# fnordlichtmini_v4.net
KiCad netlist of a schematic drawn in EAGLE
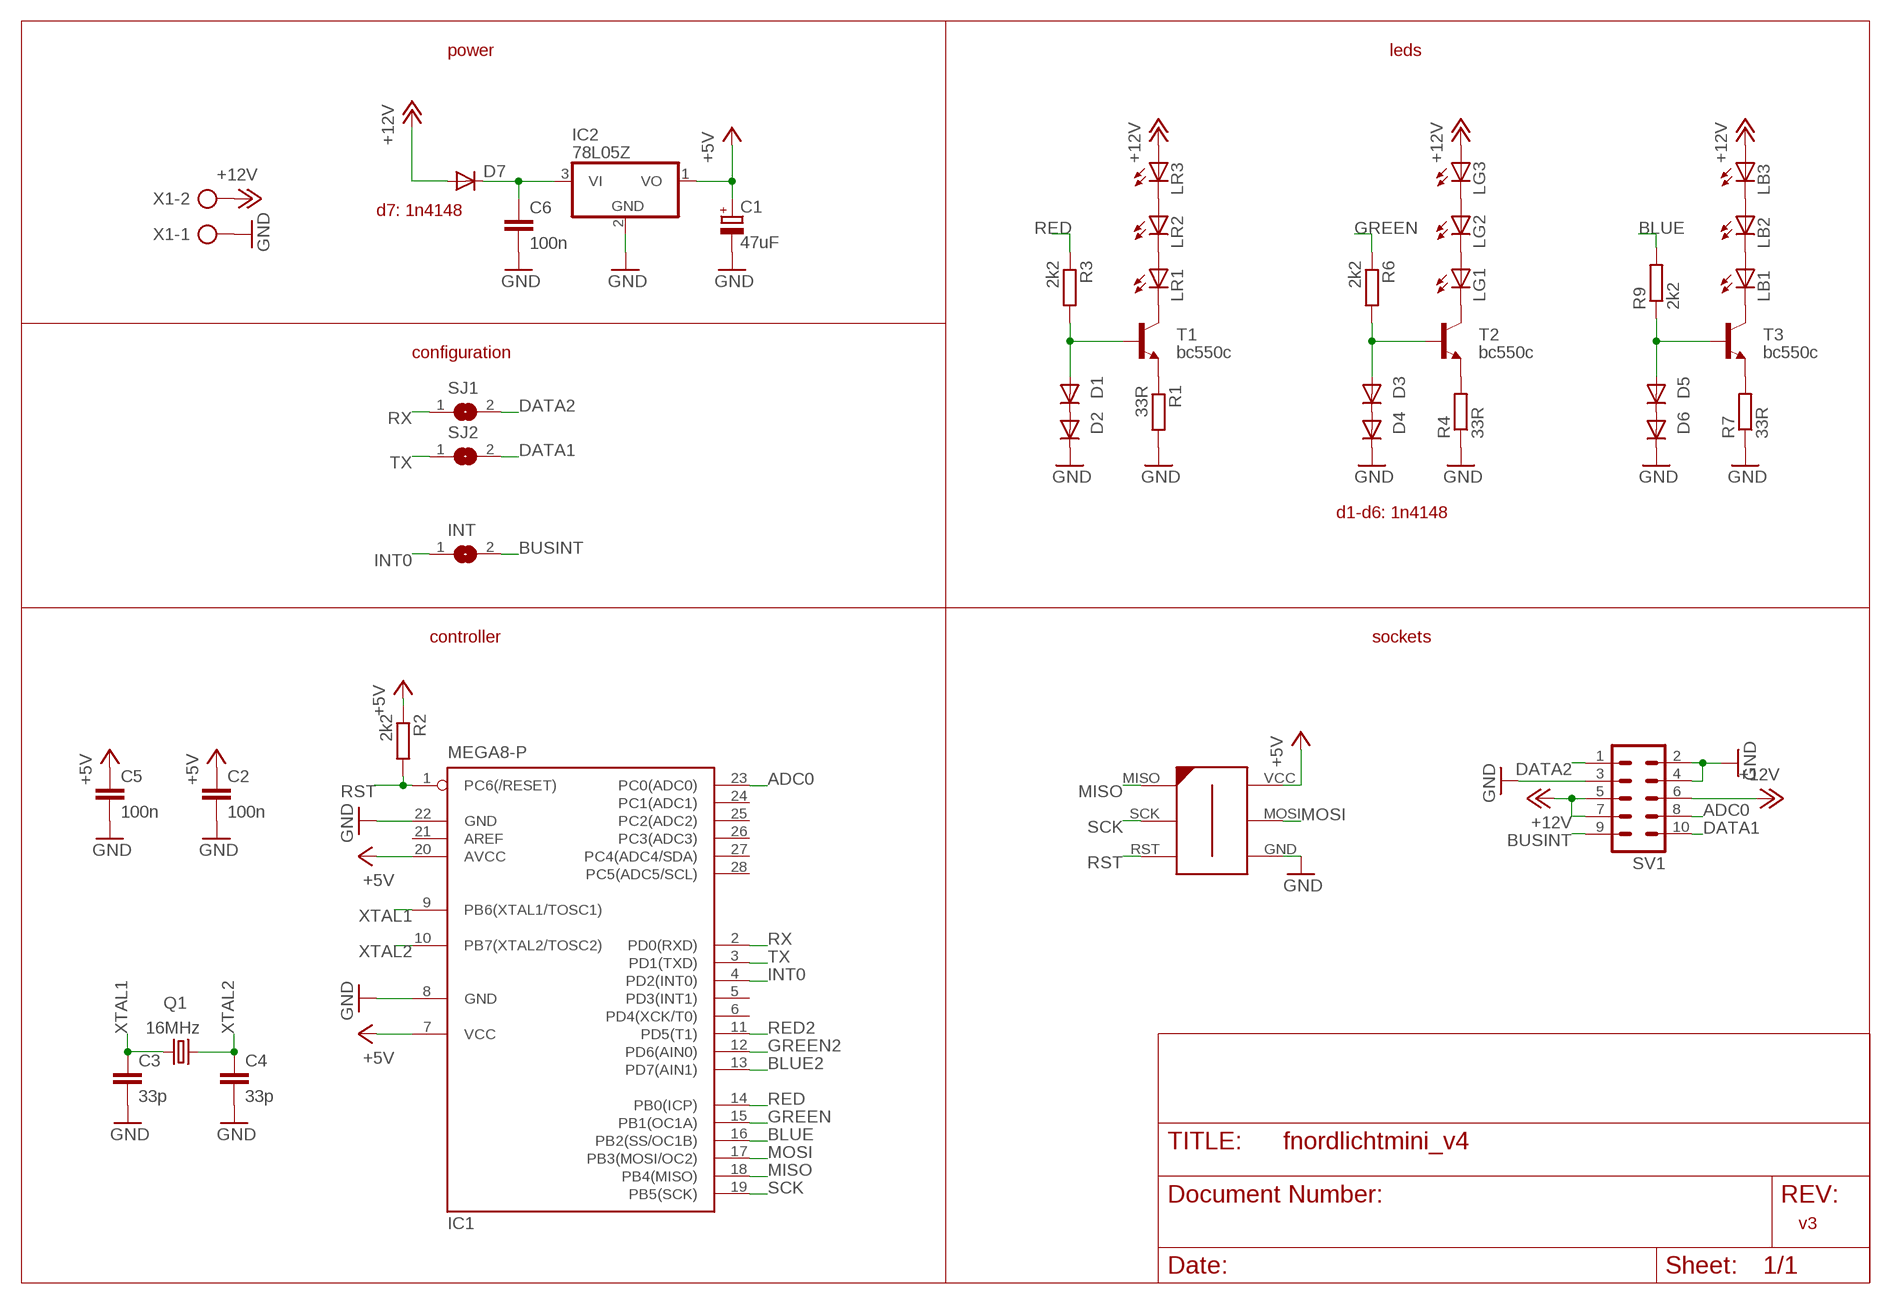
[diagram p0: schematic, sheet 1]

(export (version "E")
  (design (tool "Eeschema 10.0.6"))
  (components
    (comp (ref "C1")
      (value "47uF")
      (footprint "eagle-import:E2-5")
      (libsource (lib "eagle-import") (part "CPOL-EUE2-5"))
    )
    (comp (ref "C2")
      (value "100n")
      (footprint "eagle-import:C025-024X044")
      (libsource (lib "eagle-import") (part "C-EU025-024X044"))
    )
    (comp (ref "C3")
      (value "33p")
      (footprint "eagle-import:C025-024X044")
      (libsource (lib "eagle-import") (part "C-EU025-024X044"))
    )
    (comp (ref "C4")
      (value "33p")
      (footprint "eagle-import:C025-024X044")
      (libsource (lib "eagle-import") (part "C-EU025-024X044"))
    )
    (comp (ref "C5")
      (value "100n")
      (footprint "eagle-import:C025-024X044")
      (libsource (lib "eagle-import") (part "C-EU025-024X044"))
    )
    (comp (ref "C6")
      (value "100n")
      (footprint "eagle-import:C025-024X044")
      (libsource (lib "eagle-import") (part "C-EU025-024X044"))
    )
    (comp (ref "D1")
      (value "DIODE-D-2.5")
      (footprint "eagle-import:D-2.5")
      (libsource (lib "eagle-import") (part "DIODE-D-2.5"))
    )
    (comp (ref "D2")
      (value "DIODE-D-2.5")
      (footprint "eagle-import:D-2.5")
      (libsource (lib "eagle-import") (part "DIODE-D-2.5"))
    )
    (comp (ref "D3")
      (value "DIODE-D-2.5")
      (footprint "eagle-import:D-2.5")
      (libsource (lib "eagle-import") (part "DIODE-D-2.5"))
    )
    (comp (ref "D4")
      (value "DIODE-D-2.5")
      (footprint "eagle-import:D-2.5")
      (libsource (lib "eagle-import") (part "DIODE-D-2.5"))
    )
    (comp (ref "D5")
      (value "DIODE-D-2.5")
      (footprint "eagle-import:D-2.5")
      (libsource (lib "eagle-import") (part "DIODE-D-2.5"))
    )
    (comp (ref "D6")
      (value "DIODE-D-2.5")
      (footprint "eagle-import:D-2.5")
      (libsource (lib "eagle-import") (part "DIODE-D-2.5"))
    )
    (comp (ref "D7")
      (value "DIODE-D-2.5")
      (footprint "eagle-import:D-2.5")
      (libsource (lib "eagle-import") (part "DIODE-D-2.5"))
    )
    (comp (ref "IC1")
      (value "MEGA8-P")
      (footprint "eagle-import:DIL28-3")
      (libsource (lib "eagle-import") (part "MEGA8-P"))
    )
    (comp (ref "IC2")
      (value "78L05Z")
      (footprint "eagle-import:TO92")
      (libsource (lib "eagle-import") (part "78ZL05"))
    )
    (comp (ref "INT") (value "SJ") (footprint "eagle-import:SJ") (libsource (lib "eagle-import") (part "SJ")))
    (comp (ref "LB1")
      (value "LED5MM")
      (footprint "eagle-import:LED5MM")
      (libsource (lib "eagle-import") (part "LED5MM"))
    )
    (comp (ref "LB2")
      (value "LED5MM")
      (footprint "eagle-import:LED5MM")
      (libsource (lib "eagle-import") (part "LED5MM"))
    )
    (comp (ref "LB3")
      (value "LED5MM")
      (footprint "eagle-import:LED5MM")
      (libsource (lib "eagle-import") (part "LED5MM"))
    )
    (comp (ref "LG1")
      (value "LED5MM")
      (footprint "eagle-import:LED5MM")
      (libsource (lib "eagle-import") (part "LED5MM"))
    )
    (comp (ref "LG2")
      (value "LED5MM")
      (footprint "eagle-import:LED5MM")
      (libsource (lib "eagle-import") (part "LED5MM"))
    )
    (comp (ref "LG3")
      (value "LED5MM")
      (footprint "eagle-import:LED5MM")
      (libsource (lib "eagle-import") (part "LED5MM"))
    )
    (comp (ref "LR1")
      (value "LED5MM")
      (footprint "eagle-import:LED5MM")
      (libsource (lib "eagle-import") (part "LED5MM"))
    )
    (comp (ref "LR2")
      (value "LED5MM")
      (footprint "eagle-import:LED5MM")
      (libsource (lib "eagle-import") (part "LED5MM"))
    )
    (comp (ref "LR3")
      (value "LED5MM")
      (footprint "eagle-import:LED5MM")
      (libsource (lib "eagle-import") (part "LED5MM"))
    )
    (comp (ref "Q1")
      (value "16MHz")
      (footprint "eagle-import:HC49U-V")
      (libsource (lib "eagle-import") (part "CRYSTALHC49U-V"))
    )
    (comp (ref "R1")
      (value "33R")
      (footprint "eagle-import:0204V")
      (libsource (lib "eagle-import") (part "R-EU_0204/2V"))
    )
    (comp (ref "R2")
      (value "2k2")
      (footprint "eagle-import:0204V")
      (libsource (lib "eagle-import") (part "R-EU_0204/2V"))
    )
    (comp (ref "R3")
      (value "2k2")
      (footprint "eagle-import:0204V")
      (libsource (lib "eagle-import") (part "R-EU_0204/2V"))
    )
    (comp (ref "R4")
      (value "33R")
      (footprint "eagle-import:0204V")
      (libsource (lib "eagle-import") (part "R-EU_0204/2V"))
    )
    (comp (ref "R6")
      (value "2k2")
      (footprint "eagle-import:0204V")
      (libsource (lib "eagle-import") (part "R-EU_0204/2V"))
    )
    (comp (ref "R7")
      (value "33R")
      (footprint "eagle-import:0204V")
      (libsource (lib "eagle-import") (part "R-EU_0204/2V"))
    )
    (comp (ref "R9")
      (value "2k2")
      (footprint "eagle-import:0204V")
      (libsource (lib "eagle-import") (part "R-EU_0204/2V"))
    )
    (comp (ref "SJ1") (value "SJ") (footprint "eagle-import:SJ") (libsource (lib "eagle-import") (part "SJ")))
    (comp (ref "SJ2") (value "SJ") (footprint "eagle-import:SJ") (libsource (lib "eagle-import") (part "SJ")))
    (comp (ref "SV1")
      (value "MA05-2")
      (footprint "eagle-import:MA05-2")
      (libsource (lib "eagle-import") (part "MA05-2"))
    )
    (comp (ref "T1")
      (value "bc550c")
      (footprint "eagle-import:TO92")
      (libsource (lib "eagle-import") (part "-NPN-TO92"))
    )
    (comp (ref "T2")
      (value "bc550c")
      (footprint "eagle-import:TO92")
      (libsource (lib "eagle-import") (part "-NPN-TO92"))
    )
    (comp (ref "T3")
      (value "bc550c")
      (footprint "eagle-import:TO92")
      (libsource (lib "eagle-import") (part "-NPN-TO92"))
    )
    (comp (ref "U$1")
      (value "AVR-ISP-6-EDGE")
      (footprint "eagle-import:6PAD_ISP")
      (libsource (lib "eagle-import") (part "AVR-ISP-6-EDGE"))
    )
    (comp (ref "X1")
      (value "AK500/2")
      (footprint "eagle-import:AK500_2")
      (libsource (lib "eagle-import") (part "AK500/2"))
    )
  )
  (nets
    (net (code "1") (name "+5V") (class "Default")
      (node (ref "C1") (pin "+") (pinfunction "+_+") (pintype "passive"))
      (node (ref "C2") (pin "1") (pinfunction "1_1") (pintype "passive"))
      (node (ref "C5") (pin "1") (pinfunction "1_1") (pintype "passive"))
      (node (ref "IC1") (pin "20") (pinfunction "AVCC_20") (pintype "power_in"))
      (node (ref "IC1") (pin "7") (pinfunction "VCC_7") (pintype "power_in"))
      (node (ref "IC2") (pin "1") (pinfunction "VO_1") (pintype "passive"))
      (node (ref "R2") (pin "1") (pinfunction "1_1") (pintype "passive"))
      (node (ref "U$1") (pin "VCC") (pinfunction "P$6_VCC") (pintype "bidirectional"))
    )
    (net (code "2") (name "+12V") (class "Default")
      (node (ref "D7") (pin "A") (pinfunction "A_A") (pintype "passive"))
      (node (ref "LB3") (pin "A") (pinfunction "A_A") (pintype "passive"))
      (node (ref "LG3") (pin "A") (pinfunction "A_A") (pintype "passive"))
      (node (ref "LR3") (pin "A") (pinfunction "A_A") (pintype "passive"))
      (node (ref "SV1") (pin "5") (pinfunction "5_5") (pintype "passive"))
      (node (ref "SV1") (pin "6") (pinfunction "6_6") (pintype "passive"))
      (node (ref "SV1") (pin "7") (pinfunction "7_7") (pintype "passive"))
      (node (ref "X1") (pin "2") (pinfunction "KL_2") (pintype "passive"))
    )
    (net (code "3") (name "/ADC0") (class "Default")
      (node (ref "IC1") (pin "23") (pinfunction "PC0(ADC0)_23") (pintype "bidirectional"))
      (node (ref "SV1") (pin "8") (pinfunction "8_8") (pintype "passive"))
    )
    (net (code "4") (name "/BLUE") (class "Default")
      (node (ref "IC1") (pin "16") (pinfunction "PB2(SS/OC1B)_16") (pintype "bidirectional"))
      (node (ref "R9") (pin "2") (pinfunction "2_2") (pintype "passive"))
    )
    (net (code "5") (name "/BLUE2") (class "Default")
      (node (ref "IC1") (pin "13") (pinfunction "PD7(AIN1)_13") (pintype "bidirectional"))
    )
    (net (code "6") (name "/BUSINT") (class "Default")
      (node (ref "INT") (pin "2") (pinfunction "2_2") (pintype "passive"))
      (node (ref "SV1") (pin "9") (pinfunction "9_9") (pintype "passive"))
    )
    (net (code "7") (name "/DATA1") (class "Default")
      (node (ref "SJ2") (pin "2") (pinfunction "2_2") (pintype "passive"))
      (node (ref "SV1") (pin "10") (pinfunction "10_10") (pintype "passive"))
    )
    (net (code "8") (name "/DATA2") (class "Default")
      (node (ref "SJ1") (pin "2") (pinfunction "2_2") (pintype "passive"))
      (node (ref "SV1") (pin "1") (pinfunction "1_1") (pintype "passive"))
    )
    (net (code "9") (name "/GREEN") (class "Default")
      (node (ref "IC1") (pin "15") (pinfunction "PB1(OC1A)_15") (pintype "bidirectional"))
      (node (ref "R6") (pin "1") (pinfunction "1_1") (pintype "passive"))
    )
    (net (code "10") (name "/GREEN2") (class "Default")
      (node (ref "IC1") (pin "12") (pinfunction "PD6(AIN0)_12") (pintype "bidirectional"))
    )
    (net (code "11") (name "/INT0") (class "Default")
      (node (ref "IC1") (pin "4") (pinfunction "PD2(INT0)_4") (pintype "bidirectional"))
      (node (ref "INT") (pin "1") (pinfunction "1_1") (pintype "passive"))
    )
    (net (code "12") (name "/MISO") (class "Default")
      (node (ref "IC1") (pin "18") (pinfunction "PB4(MISO)_18") (pintype "bidirectional"))
      (node (ref "U$1") (pin "MISO") (pinfunction "P$1_MISO") (pintype "bidirectional"))
    )
    (net (code "13") (name "/MOSI") (class "Default")
      (node (ref "IC1") (pin "17") (pinfunction "PB3(MOSI/OC2)_17") (pintype "bidirectional"))
      (node (ref "U$1") (pin "MOSI") (pinfunction "P$5_MOSI") (pintype "bidirectional"))
    )
    (net (code "14") (name "/RED") (class "Default")
      (node (ref "IC1") (pin "14") (pinfunction "PB0(ICP)_14") (pintype "bidirectional"))
      (node (ref "R3") (pin "1") (pinfunction "1_1") (pintype "passive"))
    )
    (net (code "15") (name "/RED2") (class "Default")
      (node (ref "IC1") (pin "11") (pinfunction "PD5(T1)_11") (pintype "bidirectional"))
    )
    (net (code "16") (name "/RST") (class "Default")
      (node (ref "IC1") (pin "1") (pinfunction "PC6(/RESET)_1") (pintype "bidirectional"))
      (node (ref "R2") (pin "2") (pinfunction "2_2") (pintype "passive"))
      (node (ref "U$1") (pin "RST") (pinfunction "P$3_RST") (pintype "bidirectional"))
    )
    (net (code "17") (name "/RX") (class "Default")
      (node (ref "IC1") (pin "2") (pinfunction "PD0(RXD)_2") (pintype "bidirectional"))
      (node (ref "SJ1") (pin "1") (pinfunction "1_1") (pintype "passive"))
    )
    (net (code "18") (name "/SCK") (class "Default")
      (node (ref "IC1") (pin "19") (pinfunction "PB5(SCK)_19") (pintype "bidirectional"))
      (node (ref "U$1") (pin "SCK") (pinfunction "P$2_SCK") (pintype "bidirectional"))
    )
    (net (code "19") (name "/TX") (class "Default")
      (node (ref "IC1") (pin "3") (pinfunction "PD1(TXD)_3") (pintype "bidirectional"))
      (node (ref "SJ2") (pin "1") (pinfunction "1_1") (pintype "passive"))
    )
    (net (code "20") (name "/XTAL1") (class "Default")
      (node (ref "C3") (pin "1") (pinfunction "1_1") (pintype "passive"))
      (node (ref "IC1") (pin "9") (pinfunction "PB6(XTAL1/TOSC1)_9") (pintype "bidirectional"))
      (node (ref "Q1") (pin "1") (pinfunction "1_1") (pintype "passive"))
    )
    (net (code "21") (name "/XTAL2") (class "Default")
      (node (ref "C4") (pin "1") (pinfunction "1_1") (pintype "passive"))
      (node (ref "IC1") (pin "10") (pinfunction "PB7(XTAL2/TOSC2)_10") (pintype "bidirectional"))
      (node (ref "Q1") (pin "2") (pinfunction "2_2") (pintype "passive"))
    )
    (net (code "22") (name "GND") (class "Default")
      (node (ref "C1") (pin "-") (pinfunction "-_-") (pintype "passive"))
      (node (ref "C2") (pin "2") (pinfunction "2_2") (pintype "passive"))
      (node (ref "C3") (pin "2") (pinfunction "2_2") (pintype "passive"))
      (node (ref "C4") (pin "2") (pinfunction "2_2") (pintype "passive"))
      (node (ref "C5") (pin "2") (pinfunction "2_2") (pintype "passive"))
      (node (ref "C6") (pin "2") (pinfunction "2_2") (pintype "passive"))
      (node (ref "D2") (pin "C") (pinfunction "C_C") (pintype "passive"))
      (node (ref "D4") (pin "C") (pinfunction "C_C") (pintype "passive"))
      (node (ref "D6") (pin "C") (pinfunction "C_C") (pintype "passive"))
      (node (ref "IC1") (pin "22") (pinfunction "GND_22") (pintype "power_in"))
      (node (ref "IC1") (pin "8") (pinfunction "GND_8") (pintype "power_in"))
      (node (ref "IC2") (pin "2") (pinfunction "GND_2") (pintype "passive"))
      (node (ref "R1") (pin "2") (pinfunction "2_2") (pintype "passive"))
      (node (ref "R4") (pin "1") (pinfunction "1_1") (pintype "passive"))
      (node (ref "R7") (pin "1") (pinfunction "1_1") (pintype "passive"))
      (node (ref "SV1") (pin "2") (pinfunction "2_2") (pintype "passive"))
      (node (ref "SV1") (pin "3") (pinfunction "3_3") (pintype "passive"))
      (node (ref "SV1") (pin "4") (pinfunction "4_4") (pintype "passive"))
      (node (ref "U$1") (pin "GND") (pinfunction "P$4_GND") (pintype "bidirectional"))
      (node (ref "X1") (pin "1") (pinfunction "KL_1") (pintype "passive"))
    )
    (net (code "23") (name "Net-(D1-PadC)") (class "Default")
      (node (ref "D1") (pin "C") (pinfunction "C_C") (pintype "passive"))
      (node (ref "D2") (pin "A") (pinfunction "A_A") (pintype "passive"))
    )
    (net (code "24") (name "Net-(D3-PadC)") (class "Default")
      (node (ref "D3") (pin "C") (pinfunction "C_C") (pintype "passive"))
      (node (ref "D4") (pin "A") (pinfunction "A_A") (pintype "passive"))
    )
    (net (code "25") (name "Net-(D5-PadC)") (class "Default")
      (node (ref "D5") (pin "C") (pinfunction "C_C") (pintype "passive"))
      (node (ref "D6") (pin "A") (pinfunction "A_A") (pintype "passive"))
    )
    (net (code "26") (name "Net-(IC2-VI)") (class "Default")
      (node (ref "C6") (pin "1") (pinfunction "1_1") (pintype "passive"))
      (node (ref "D7") (pin "C") (pinfunction "C_C") (pintype "passive"))
      (node (ref "IC2") (pin "3") (pinfunction "VI_3") (pintype "input"))
    )
    (net (code "27") (name "Net-(LB1-C)") (class "Default")
      (node (ref "LB1") (pin "K") (pinfunction "C_K") (pintype "passive"))
      (node (ref "T3") (pin "3") (pinfunction "C_3") (pintype "passive"))
    )
    (net (code "28") (name "Net-(LB2-C)") (class "Default")
      (node (ref "LB1") (pin "A") (pinfunction "A_A") (pintype "passive"))
      (node (ref "LB2") (pin "K") (pinfunction "C_K") (pintype "passive"))
    )
    (net (code "29") (name "Net-(LB3-C)") (class "Default")
      (node (ref "LB2") (pin "A") (pinfunction "A_A") (pintype "passive"))
      (node (ref "LB3") (pin "K") (pinfunction "C_K") (pintype "passive"))
    )
    (net (code "30") (name "Net-(LG1-C)") (class "Default")
      (node (ref "LG1") (pin "K") (pinfunction "C_K") (pintype "passive"))
      (node (ref "T2") (pin "3") (pinfunction "C_3") (pintype "passive"))
    )
    (net (code "31") (name "Net-(LG2-C)") (class "Default")
      (node (ref "LG1") (pin "A") (pinfunction "A_A") (pintype "passive"))
      (node (ref "LG2") (pin "K") (pinfunction "C_K") (pintype "passive"))
    )
    (net (code "32") (name "Net-(LG3-C)") (class "Default")
      (node (ref "LG2") (pin "A") (pinfunction "A_A") (pintype "passive"))
      (node (ref "LG3") (pin "K") (pinfunction "C_K") (pintype "passive"))
    )
    (net (code "33") (name "Net-(LR1-C)") (class "Default")
      (node (ref "LR1") (pin "K") (pinfunction "C_K") (pintype "passive"))
      (node (ref "T1") (pin "3") (pinfunction "C_3") (pintype "passive"))
    )
    (net (code "34") (name "Net-(LR2-C)") (class "Default")
      (node (ref "LR1") (pin "A") (pinfunction "A_A") (pintype "passive"))
      (node (ref "LR2") (pin "K") (pinfunction "C_K") (pintype "passive"))
    )
    (net (code "35") (name "Net-(LR3-C)") (class "Default")
      (node (ref "LR2") (pin "A") (pinfunction "A_A") (pintype "passive"))
      (node (ref "LR3") (pin "K") (pinfunction "C_K") (pintype "passive"))
    )
    (net (code "36") (name "Net-(T1-B)") (class "Default")
      (node (ref "D1") (pin "A") (pinfunction "A_A") (pintype "passive"))
      (node (ref "R3") (pin "2") (pinfunction "2_2") (pintype "passive"))
      (node (ref "T1") (pin "2") (pinfunction "B_2") (pintype "passive"))
    )
    (net (code "37") (name "Net-(T1-E)") (class "Default")
      (node (ref "R1") (pin "1") (pinfunction "1_1") (pintype "passive"))
      (node (ref "T1") (pin "1") (pinfunction "E_1") (pintype "passive"))
    )
    (net (code "38") (name "Net-(T2-B)") (class "Default")
      (node (ref "D3") (pin "A") (pinfunction "A_A") (pintype "passive"))
      (node (ref "R6") (pin "2") (pinfunction "2_2") (pintype "passive"))
      (node (ref "T2") (pin "2") (pinfunction "B_2") (pintype "passive"))
    )
    (net (code "39") (name "Net-(T2-E)") (class "Default")
      (node (ref "R4") (pin "2") (pinfunction "2_2") (pintype "passive"))
      (node (ref "T2") (pin "1") (pinfunction "E_1") (pintype "passive"))
    )
    (net (code "40") (name "Net-(T3-B)") (class "Default")
      (node (ref "D5") (pin "A") (pinfunction "A_A") (pintype "passive"))
      (node (ref "R9") (pin "1") (pinfunction "1_1") (pintype "passive"))
      (node (ref "T3") (pin "2") (pinfunction "B_2") (pintype "passive"))
    )
    (net (code "41") (name "Net-(T3-E)") (class "Default")
      (node (ref "R7") (pin "2") (pinfunction "2_2") (pintype "passive"))
      (node (ref "T3") (pin "1") (pinfunction "E_1") (pintype "passive"))
    )
    (net (code "42") (name "unconnected-(IC1-AREF-Pad21)") (class "Default")
      (node (ref "IC1") (pin "21") (pinfunction "AREF_21") (pintype "passive"))
    )
    (net (code "43") (name "unconnected-(IC1-PC1(ADC1)-Pad24)") (class "Default")
      (node (ref "IC1") (pin "24") (pinfunction "PC1(ADC1)_24") (pintype "bidirectional"))
    )
    (net (code "44") (name "unconnected-(IC1-PC2(ADC2)-Pad25)") (class "Default")
      (node (ref "IC1") (pin "25") (pinfunction "PC2(ADC2)_25") (pintype "bidirectional"))
    )
    (net (code "45") (name "unconnected-(IC1-PC3(ADC3)-Pad26)") (class "Default")
      (node (ref "IC1") (pin "26") (pinfunction "PC3(ADC3)_26") (pintype "bidirectional"))
    )
    (net (code "46") (name "unconnected-(IC1-PC4(ADC4{slash}SDA)-Pad27)") (class "Default")
      (node (ref "IC1") (pin "27") (pinfunction "PC4(ADC4/SDA)_27") (pintype "bidirectional"))
    )
    (net (code "47") (name "unconnected-(IC1-PC5(ADC5{slash}SCL)-Pad28)") (class "Default")
      (node (ref "IC1") (pin "28") (pinfunction "PC5(ADC5/SCL)_28") (pintype "bidirectional"))
    )
    (net (code "48") (name "unconnected-(IC1-PD3(INT1)-Pad5)") (class "Default")
      (node (ref "IC1") (pin "5") (pinfunction "PD3(INT1)_5") (pintype "bidirectional"))
    )
    (net (code "49") (name "unconnected-(IC1-PD4(XCK{slash}T0)-Pad6)") (class "Default")
      (node (ref "IC1") (pin "6") (pinfunction "PD4(XCK/T0)_6") (pintype "bidirectional"))
    )
  )
)
